# sch.net
KiCad netlist of a schematic drawn in Altium Designer
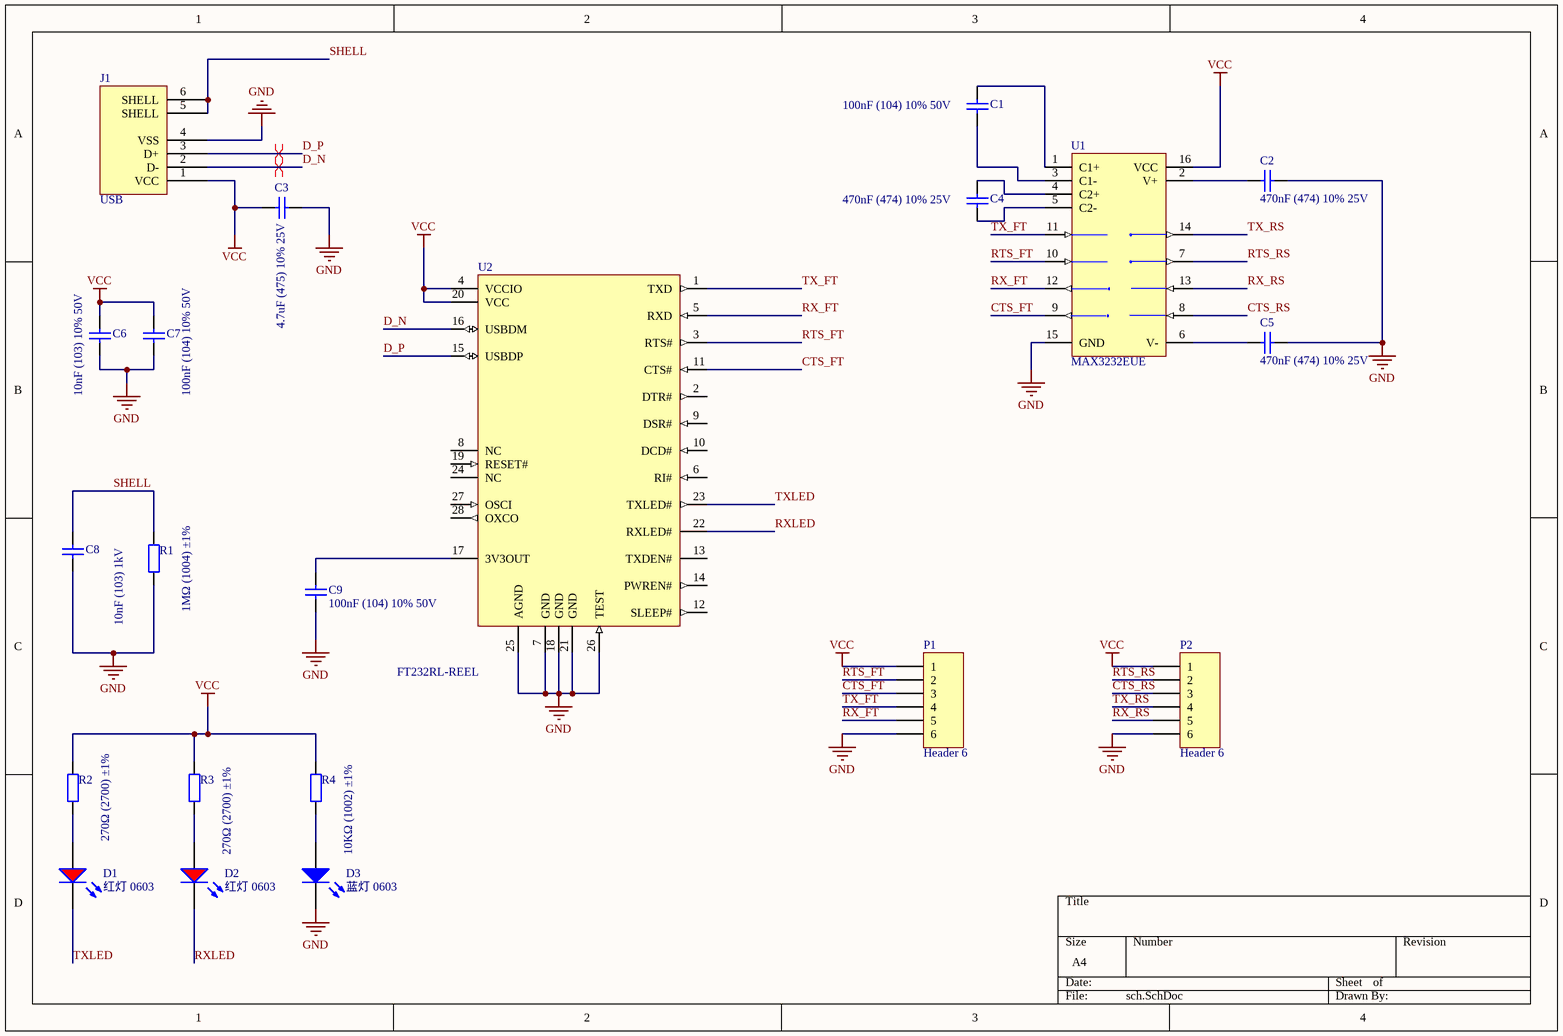
[diagram p0: sch.SchDoc]

(export (version "E")
  (design (tool "Eeschema 10.0.6"))
  (components
    (comp (ref "C1")
      (value "100nF (104) 10% 50V")
      (footprint "0603_C")
      (description "贴片电容")
      (libsource (lib "jlc") (part "0603 100nF (104) 10% 50V"))
    )
    (comp (ref "C2")
      (value "470nF (474) 10% 25V")
      (footprint "0603_C")
      (description "贴片电容")
      (libsource (lib "jlc") (part "0603 470nF (474) 10% 25V"))
    )
    (comp (ref "C3")
      (value "4.7uF (475) 10% 25V")
      (footprint "0805_C")
      (description "贴片电容")
      (libsource (lib "jlc") (part "0805 4.7uF (475) 10% 25V"))
    )
    (comp (ref "C4")
      (value "470nF (474) 10% 25V")
      (footprint "0603_C")
      (description "贴片电容")
      (libsource (lib "jlc") (part "0603 470nF (474) 10% 25V"))
    )
    (comp (ref "C5")
      (value "470nF (474) 10% 25V")
      (footprint "0603_C")
      (description "贴片电容")
      (libsource (lib "jlc") (part "0603 470nF (474) 10% 25V"))
    )
    (comp (ref "C6")
      (value "10nF (103) 10% 50V")
      (footprint "0603_C")
      (description "贴片电容")
      (libsource (lib "jlc") (part "0603 10nF (103) 10% 50V"))
    )
    (comp (ref "C7")
      (value "100nF (104) 10% 50V")
      (footprint "0603_C")
      (description "贴片电容")
      (libsource (lib "jlc") (part "0603 100nF (104) 10% 50V"))
    )
    (comp (ref "C8")
      (value "10nF (103) 1kV")
      (footprint "1206_C")
      (description "贴片电容")
      (libsource (lib "jlc") (part "1206 10nF (103) 10% 50V"))
    )
    (comp (ref "C9")
      (value "100nF (104) 10% 50V")
      (footprint "0603_C")
      (description "贴片电容")
      (libsource (lib "jlc") (part "0603 100nF (104) 10% 50V"))
    )
    (comp (ref "D1")
      (value "红灯 0603")
      (footprint "0603_LED_S1")
      (description "发光二极管")
      (libsource (lib "jlc") (part "0603 红灯"))
    )
    (comp (ref "D2")
      (value "红灯 0603")
      (footprint "0603_LED_S1")
      (description "发光二极管")
      (libsource (lib "jlc") (part "0603 红灯"))
    )
    (comp (ref "D3")
      (value "蓝灯 0603")
      (footprint "0603_LED_S1")
      (description "发光二极管")
      (libsource (lib "jlc") (part "0603 蓝灯"))
    )
    (comp (ref "J1")
      (value "USB")
      (footprint "USB_B1")
      (description "USB接口")
      (libsource (lib "HDR_Fszhang") (part "USB"))
    )
    (comp (ref "P1")
      (value "Header 6")
      (footprint "HDR1X6")
      (description "Header, 6-Pin")
      (fields (field (name "PUBLISHER") "Altium Limited"))
      (libsource (lib "Miscellaneous Connectors") (part "Header 6"))
    )
    (comp (ref "P2")
      (value "Header 6")
      (footprint "HDR1X6")
      (description "Header, 6-Pin")
      (fields (field (name "PUBLISHER") "Altium Limited"))
      (libsource (lib "Miscellaneous Connectors") (part "Header 6"))
    )
    (comp (ref "R1")
      (value "1MΩ (1004) ±1%")
      (footprint "0805_R")
      (description "贴片电阻")
      (libsource (lib "jlc") (part "0805 1MΩ (1004) 1%"))
    )
    (comp (ref "R2")
      (value "270Ω (2700) ±1%")
      (footprint "0603_R")
      (description "贴片电阻")
      (libsource (lib "jlc") (part "0603 270Ω (2700) 1%"))
    )
    (comp (ref "R3")
      (value "270Ω (2700) ±1%")
      (footprint "0603_R")
      (description "贴片电阻")
      (libsource (lib "jlc") (part "0603 270Ω (2700) 1%"))
    )
    (comp (ref "R4")
      (value "10KΩ (1002) ±1%")
      (footprint "0603_R")
      (description "贴片电阻")
      (libsource (lib "jlc") (part "0603 10KΩ (1002) 1%"))
    )
    (comp (ref "U1")
      (value "MAX3232EUE")
      (footprint "TSSOP-16")
      (description "RS232")
      (libsource (lib "jlc") (part "SP3232EEY-L/TR"))
    )
    (comp (ref "U2")
      (value "FT232RL-REEL")
      (footprint "SSOP-28_208mil")
      (description "USB")
      (libsource (lib "jlc") (part "FT232RL-REEL"))
    )
  )
  (nets
    (net (code "1") (name "/CTS_FT") (class "Default")
      (node (ref "P1") (pin "3") (pinfunction "3_3") (pintype "passive"))
      (node (ref "U1") (pin "9") (pinfunction "R2OUT_9") (pintype "output"))
      (node (ref "U2") (pin "11") (pinfunction "CTS#_11") (pintype "input"))
    )
    (net (code "2") (name "/CTS_RS") (class "Default")
      (node (ref "P2") (pin "3") (pinfunction "3_3") (pintype "passive"))
      (node (ref "U1") (pin "8") (pinfunction "R2IN_8") (pintype "input"))
    )
    (net (code "3") (name "/D_N") (class "Default")
      (node (ref "J1") (pin "2") (pinfunction "D-_2") (pintype "passive"))
      (node (ref "U2") (pin "16") (pinfunction "USBDM_16") (pintype "bidirectional"))
    )
    (net (code "4") (name "/D_P") (class "Default")
      (node (ref "J1") (pin "3") (pinfunction "D+_3") (pintype "passive"))
      (node (ref "U2") (pin "15") (pinfunction "USBDP_15") (pintype "bidirectional"))
    )
    (net (code "5") (name "/RTS_FT") (class "Default")
      (node (ref "P1") (pin "2") (pinfunction "2_2") (pintype "passive"))
      (node (ref "U1") (pin "10") (pinfunction "T2IN_10") (pintype "input"))
      (node (ref "U2") (pin "3") (pinfunction "RTS#_3") (pintype "output"))
    )
    (net (code "6") (name "/RTS_RS") (class "Default")
      (node (ref "P2") (pin "2") (pinfunction "2_2") (pintype "passive"))
      (node (ref "U1") (pin "7") (pinfunction "T2OUT_7") (pintype "output"))
    )
    (net (code "7") (name "/RXLED") (class "Default")
      (node (ref "D2") (pin "K") (pinfunction "K_K") (pintype "passive"))
      (node (ref "U2") (pin "22") (pinfunction "RXLED#_22") (pintype "open_collector"))
    )
    (net (code "8") (name "/RX_FT") (class "Default")
      (node (ref "P1") (pin "5") (pinfunction "5_5") (pintype "passive"))
      (node (ref "U1") (pin "12") (pinfunction "R1OUT_12") (pintype "output"))
      (node (ref "U2") (pin "5") (pinfunction "RXD_5") (pintype "input"))
    )
    (net (code "9") (name "/RX_RS") (class "Default")
      (node (ref "P2") (pin "5") (pinfunction "5_5") (pintype "passive"))
      (node (ref "U1") (pin "13") (pinfunction "R1IN_13") (pintype "input"))
    )
    (net (code "10") (name "/SHELL") (class "Default")
      (node (ref "C8") (pin "2") (pinfunction "2_2") (pintype "passive"))
      (node (ref "J1") (pin "5") (pinfunction "SHELL_5") (pintype "passive"))
      (node (ref "J1") (pin "6") (pinfunction "SHELL_6") (pintype "passive"))
      (node (ref "R1") (pin "2") (pinfunction "2_2") (pintype "passive"))
    )
    (net (code "11") (name "/TXLED") (class "Default")
      (node (ref "D1") (pin "K") (pinfunction "K_K") (pintype "passive"))
      (node (ref "U2") (pin "23") (pinfunction "TXLED#_23") (pintype "output"))
    )
    (net (code "12") (name "/TX_FT") (class "Default")
      (node (ref "P1") (pin "4") (pinfunction "4_4") (pintype "passive"))
      (node (ref "U1") (pin "11") (pinfunction "T1IN_11") (pintype "input"))
      (node (ref "U2") (pin "1") (pinfunction "TXD_1") (pintype "output"))
    )
    (net (code "13") (name "/TX_RS") (class "Default")
      (node (ref "P2") (pin "4") (pinfunction "4_4") (pintype "passive"))
      (node (ref "U1") (pin "14") (pinfunction "T1OUT_14") (pintype "output"))
    )
    (net (code "14") (name "GND") (class "Default")
      (node (ref "C2") (pin "2") (pinfunction "2_2") (pintype "passive"))
      (node (ref "C3") (pin "2") (pinfunction "2_2") (pintype "passive"))
      (node (ref "C5") (pin "2") (pinfunction "2_2") (pintype "passive"))
      (node (ref "C6") (pin "1") (pinfunction "1_1") (pintype "passive"))
      (node (ref "C7") (pin "1") (pinfunction "1_1") (pintype "passive"))
      (node (ref "C8") (pin "1") (pinfunction "1_1") (pintype "passive"))
      (node (ref "C9") (pin "1") (pinfunction "1_1") (pintype "passive"))
      (node (ref "D3") (pin "K") (pinfunction "K_K") (pintype "passive"))
      (node (ref "J1") (pin "4") (pinfunction "VSS_4") (pintype "passive"))
      (node (ref "P1") (pin "6") (pinfunction "6_6") (pintype "passive"))
      (node (ref "P2") (pin "6") (pinfunction "6_6") (pintype "passive"))
      (node (ref "R1") (pin "1") (pinfunction "1_1") (pintype "passive"))
      (node (ref "U1") (pin "15") (pinfunction "GND_15") (pintype "power_in"))
      (node (ref "U2") (pin "18") (pinfunction "GND_18") (pintype "power_in"))
      (node (ref "U2") (pin "21") (pinfunction "GND_21") (pintype "power_in"))
      (node (ref "U2") (pin "25") (pinfunction "AGND_25") (pintype "power_in"))
      (node (ref "U2") (pin "26") (pinfunction "TEST_26") (pintype "input"))
      (node (ref "U2") (pin "7") (pinfunction "GND_7") (pintype "power_in"))
    )
    (net (code "15") (name "Net-(D1-PadA)") (class "Default")
      (node (ref "D1") (pin "A") (pinfunction "A_A") (pintype "passive"))
      (node (ref "R2") (pin "1") (pinfunction "1_1") (pintype "passive"))
    )
    (net (code "16") (name "Net-(D2-PadA)") (class "Default")
      (node (ref "D2") (pin "A") (pinfunction "A_A") (pintype "passive"))
      (node (ref "R3") (pin "1") (pinfunction "1_1") (pintype "passive"))
    )
    (net (code "17") (name "Net-(D3-PadA)") (class "Default")
      (node (ref "D3") (pin "A") (pinfunction "A_A") (pintype "passive"))
      (node (ref "R4") (pin "1") (pinfunction "1_1") (pintype "passive"))
    )
    (net (code "18") (name "Net-(U1-C1+)") (class "Default")
      (node (ref "C1") (pin "2") (pinfunction "2_2") (pintype "passive"))
      (node (ref "U1") (pin "1") (pinfunction "C1+_1") (pintype "passive"))
    )
    (net (code "19") (name "Net-(U1-C1-)") (class "Default")
      (node (ref "C1") (pin "1") (pinfunction "1_1") (pintype "passive"))
      (node (ref "U1") (pin "3") (pinfunction "C1-_3") (pintype "passive"))
    )
    (net (code "20") (name "Net-(U1-C2+)") (class "Default")
      (node (ref "C4") (pin "2") (pinfunction "2_2") (pintype "passive"))
      (node (ref "U1") (pin "4") (pinfunction "C2+_4") (pintype "passive"))
    )
    (net (code "21") (name "Net-(U1-C2-)") (class "Default")
      (node (ref "C4") (pin "1") (pinfunction "1_1") (pintype "passive"))
      (node (ref "U1") (pin "5") (pinfunction "C2-_5") (pintype "passive"))
    )
    (net (code "22") (name "Net-(U1-V+)") (class "Default")
      (node (ref "C2") (pin "1") (pinfunction "1_1") (pintype "passive"))
      (node (ref "U1") (pin "2") (pinfunction "V+_2") (pintype "power_in"))
    )
    (net (code "23") (name "Net-(U1-V-)") (class "Default")
      (node (ref "C5") (pin "1") (pinfunction "1_1") (pintype "passive"))
      (node (ref "U1") (pin "6") (pinfunction "V-_6") (pintype "power_in"))
    )
    (net (code "24") (name "Net-(U2-3V3OUT)") (class "Default")
      (node (ref "C9") (pin "2") (pinfunction "2_2") (pintype "passive"))
      (node (ref "U2") (pin "17") (pinfunction "3V3OUT_17") (pintype "power_in"))
    )
    (net (code "25") (name "VCC") (class "Default")
      (node (ref "C3") (pin "1") (pinfunction "1_1") (pintype "passive"))
      (node (ref "C6") (pin "2") (pinfunction "2_2") (pintype "passive"))
      (node (ref "C7") (pin "2") (pinfunction "2_2") (pintype "passive"))
      (node (ref "J1") (pin "1") (pinfunction "VCC_1") (pintype "passive"))
      (node (ref "P1") (pin "1") (pinfunction "1_1") (pintype "passive"))
      (node (ref "P2") (pin "1") (pinfunction "1_1") (pintype "passive"))
      (node (ref "R2") (pin "2") (pinfunction "2_2") (pintype "passive"))
      (node (ref "R3") (pin "2") (pinfunction "2_2") (pintype "passive"))
      (node (ref "R4") (pin "2") (pinfunction "2_2") (pintype "passive"))
      (node (ref "U1") (pin "16") (pinfunction "VCC_16") (pintype "power_in"))
      (node (ref "U2") (pin "20") (pinfunction "VCC_20") (pintype "power_in"))
      (node (ref "U2") (pin "4") (pinfunction "VCCIO_4") (pintype "power_in"))
    )
    (net (code "26") (name "unconnected-(U2-DCD#-Pad10)") (class "Default")
      (node (ref "U2") (pin "10") (pinfunction "DCD#_10") (pintype "input"))
    )
    (net (code "27") (name "unconnected-(U2-DSR#-Pad9)") (class "Default")
      (node (ref "U2") (pin "9") (pinfunction "DSR#_9") (pintype "input"))
    )
    (net (code "28") (name "unconnected-(U2-DTR#-Pad2)") (class "Default")
      (node (ref "U2") (pin "2") (pinfunction "DTR#_2") (pintype "output"))
    )
    (net (code "29") (name "unconnected-(U2-NC-Pad8)") (class "Default")
      (node (ref "U2") (pin "8") (pinfunction "NC_8") (pintype "passive"))
    )
    (net (code "30") (name "unconnected-(U2-NC-Pad24)") (class "Default")
      (node (ref "U2") (pin "24") (pinfunction "NC_24") (pintype "passive"))
    )
    (net (code "31") (name "unconnected-(U2-OSCI-Pad27)") (class "Default")
      (node (ref "U2") (pin "27") (pinfunction "OSCI_27") (pintype "input"))
    )
    (net (code "32") (name "unconnected-(U2-OXCO-Pad28)") (class "Default")
      (node (ref "U2") (pin "28") (pinfunction "OXCO_28") (pintype "output"))
    )
    (net (code "33") (name "unconnected-(U2-PWREN#-Pad14)") (class "Default")
      (node (ref "U2") (pin "14") (pinfunction "PWREN#_14") (pintype "output"))
    )
    (net (code "34") (name "unconnected-(U2-RESET#-Pad19)") (class "Default")
      (node (ref "U2") (pin "19") (pinfunction "RESET#_19") (pintype "input"))
    )
    (net (code "35") (name "unconnected-(U2-RI#-Pad6)") (class "Default")
      (node (ref "U2") (pin "6") (pinfunction "RI#_6") (pintype "input"))
    )
    (net (code "36") (name "unconnected-(U2-SLEEP#-Pad12)") (class "Default")
      (node (ref "U2") (pin "12") (pinfunction "SLEEP#_12") (pintype "output"))
    )
    (net (code "37") (name "unconnected-(U2-TXDEN#-Pad13)") (class "Default")
      (node (ref "U2") (pin "13") (pinfunction "TXDEN#_13") (pintype "open_collector"))
    )
  )
)
